# encoder.net
KiCad netlist of a schematic drawn in Altium Designer
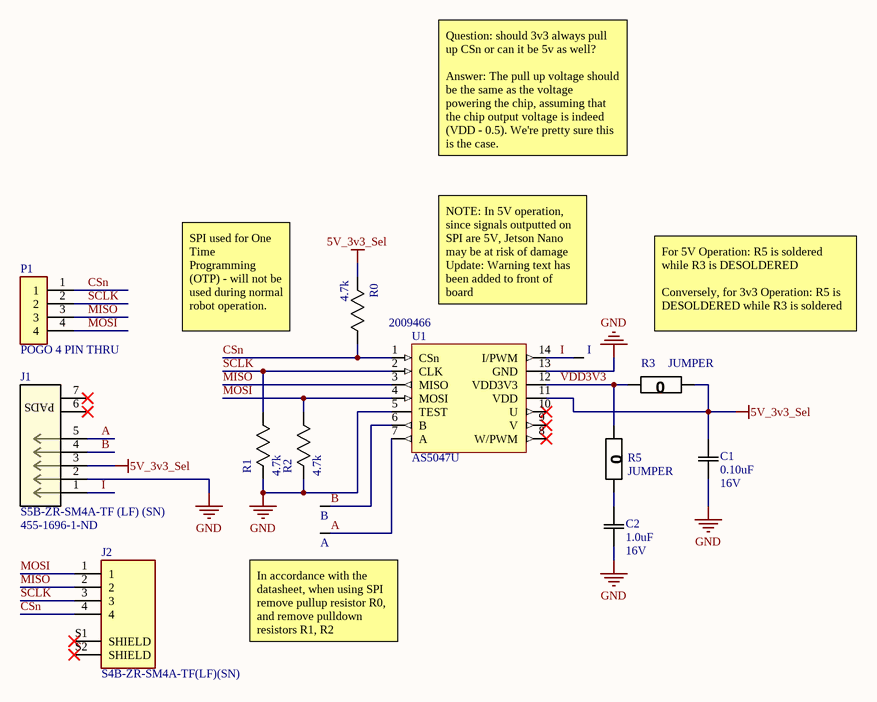
[diagram p0: encoder.SchDoc]

(export (version "E")
  (design (tool "Eeschema 10.0.6"))
  (components
    (comp (ref "A")
      (value "Test Point (Via)")
      (footprint "TP")
      (libsource (lib "AltiumLibraries") (part "Test Point (Via)"))
    )
    (comp (ref "B")
      (value "Test Point (Via)")
      (footprint "TP")
      (libsource (lib "AltiumLibraries") (part "Test Point (Via)"))
    )
    (comp (ref "C1")
      (value "0.10uF")
      (footprint "0603")
      (description "CAP CER 0.10UF 16V X5R 0603/0805")
      (fields (field (name "TOLERANCE") "10%") (field (name "RATING") "16V"))
      (libsource (lib "AltiumLibraries") (part "CAP 0.10uF 16V"))
    )
    (comp (ref "C2")
      (value "1.0uF")
      (footprint "0603")
      (description "CAP CER 1.0UF 16V X5R 0603/0805")
      (fields (field (name "TOLERANCE") "10%") (field (name "RATING") "16V"))
      (libsource (lib "AltiumLibraries") (part "CAP 1.0uF 16V"))
    )
    (comp (ref "I")
      (value "Test Point (Via)")
      (footprint "TP")
      (libsource (lib "AltiumLibraries") (part "Test Point (Via)"))
    )
    (comp (ref "J1")
      (value "S5B-ZR-SM4A-TF (LF) (SN)")
      (footprint "JST_S5B-ZR-SM4A-TF")
      (description "Connector Header Surface Mount, Right Angle 5 position 0.059\" (1.50mm)")
      (fields
        (field (name "SUPPLIER PART NUMBER 1") "455-1696-1-ND")
        (field (name "COPYRIGHT") "Copyright (C) 2021 Ultra Librarian. All rights reserved.")
      )
      (libsource (lib "AltiumLibraries") (part "CN 5POS JST ZR RA"))
    )
    (comp (ref "J2")
      (value "S4B-ZR-SM4A-TF(LF)(SN)")
      (footprint "JST_S4B-ZR-SM4A-TF(LF)(SN)")
      (description "Connector Header Surface Mount, Right Angle 4 position 0.059 (1.50mm)")
      (fields (field (name "MF") "JST Sales"))
      (libsource (lib "AltiumLibraries") (part "S4B-ZR-SM4A-TF(LF)(SN)"))
    )
    (comp (ref "P1")
      (value "POGO 4 PIN THRU")
      (footprint "POGO 4 PIN THRU")
      (description "4 pin POGO Holes 0.100\" Pitch")
      (libsource (lib "AltiumLibraries") (part "POGO 4 PIN THRU"))
    )
    (comp (ref "R0")
      (value "4.7k")
      (footprint "0603")
      (description "RES SMD 4.7k OHM 5% 1/8W 0805")
      (fields (field (name "TOLERANCE") "5%"))
      (libsource (lib "AltiumLibraries") (part "RES 4.7k 1/8W - 5%"))
    )
    (comp (ref "R1")
      (value "4.7k")
      (footprint "0603")
      (description "RES SMD 4.7k OHM 5% 1/8W 0805")
      (fields (field (name "TOLERANCE") "5%"))
      (libsource (lib "AltiumLibraries") (part "RES 4.7k 1/8W - 5%"))
    )
    (comp (ref "R2")
      (value "4.7k")
      (footprint "0603")
      (description "RES SMD 4.7k OHM 5% 1/8W 0805")
      (fields (field (name "TOLERANCE") "5%"))
      (libsource (lib "") (part "RES 4.7k 1/8W - 5%_1"))
    )
    (comp (ref "R3")
      (value "JUMPER")
      (footprint "0603")
      (description "RES SMD 0 OHM JUMPER GENERIC 0805/0603")
      (libsource (lib "AltiumLibraries") (part "RES 0 JUMPER"))
    )
    (comp (ref "R5")
      (value "JUMPER")
      (footprint "0603")
      (description "RES SMD 0 OHM JUMPER GENERIC 0805/0603")
      (libsource (lib "AltiumLibraries") (part "RES 0 JUMPER"))
    )
    (comp (ref "U1")
      (value "AS5047U")
      (footprint "AS5047U")
      (description "14-Bit On-Axis Magnetic Rotary Position Sensor with Up to 14-Bit Binary Incremental Pulse Count")
      (fields (field (name "SUPPLIER PART NUMBER 1") "2009466"))
      (libsource (lib "AltiumLibraries") (part "AS5047U"))
    )
  )
  (nets
    (net (code "1") (name "/A") (class "Default")
      (node (ref "A") (pin "1") (pinfunction "1_1") (pintype "passive"))
      (node (ref "J1") (pin "5") (pinfunction "5_5") (pintype "passive"))
      (node (ref "U1") (pin "7") (pinfunction "A_7") (pintype "output"))
    )
    (net (code "2") (name "/B") (class "Default")
      (node (ref "B") (pin "1") (pinfunction "1_1") (pintype "passive"))
      (node (ref "J1") (pin "4") (pinfunction "4_4") (pintype "passive"))
      (node (ref "U1") (pin "6") (pinfunction "B_6") (pintype "output"))
    )
    (net (code "3") (name "/CSn") (class "Default")
      (node (ref "J2") (pin "4") (pinfunction "4_4") (pintype "passive"))
      (node (ref "P1") (pin "1") (pinfunction "1_1") (pintype "passive"))
      (node (ref "R0") (pin "1") (pinfunction "R1_1") (pintype "passive"))
      (node (ref "U1") (pin "1") (pinfunction "CSn_1") (pintype "input"))
    )
    (net (code "4") (name "/I") (class "Default")
      (node (ref "I") (pin "1") (pinfunction "1_1") (pintype "passive"))
      (node (ref "J1") (pin "1") (pinfunction "1_1") (pintype "passive"))
      (node (ref "U1") (pin "14") (pinfunction "I/PWM_14") (pintype "output"))
    )
    (net (code "5") (name "/MISO") (class "Default")
      (node (ref "J2") (pin "2") (pinfunction "2_2") (pintype "passive"))
      (node (ref "P1") (pin "3") (pinfunction "3_3") (pintype "passive"))
      (node (ref "U1") (pin "3") (pinfunction "MISO_3") (pintype "output"))
    )
    (net (code "6") (name "/MOSI") (class "Default")
      (node (ref "J2") (pin "1") (pinfunction "1_1") (pintype "passive"))
      (node (ref "P1") (pin "4") (pinfunction "4_4") (pintype "passive"))
      (node (ref "R2") (pin "1") (pinfunction "R1_1") (pintype "passive"))
      (node (ref "U1") (pin "4") (pinfunction "MOSI_4") (pintype "input"))
    )
    (net (code "7") (name "/SCLK") (class "Default")
      (node (ref "J2") (pin "3") (pinfunction "3_3") (pintype "passive"))
      (node (ref "P1") (pin "2") (pinfunction "2_2") (pintype "passive"))
      (node (ref "R1") (pin "1") (pinfunction "R1_1") (pintype "passive"))
      (node (ref "U1") (pin "2") (pinfunction "CLK_2") (pintype "input"))
    )
    (net (code "8") (name "/VDD3V3") (class "Default")
      (node (ref "R3") (pin "2") (pinfunction "R2_2") (pintype "passive"))
      (node (ref "R5") (pin "1") (pinfunction "R1_1") (pintype "passive"))
      (node (ref "U1") (pin "12") (pinfunction "VDD3V3_12") (pintype "passive"))
    )
    (net (code "9") (name "5V_3v3_Sel") (class "Default")
      (node (ref "C1") (pin "2") (pinfunction "C2_2") (pintype "passive"))
      (node (ref "J1") (pin "3") (pinfunction "3_3") (pintype "passive"))
      (node (ref "R0") (pin "2") (pinfunction "R2_2") (pintype "passive"))
      (node (ref "R3") (pin "1") (pinfunction "R1_1") (pintype "passive"))
      (node (ref "U1") (pin "11") (pinfunction "VDD_11") (pintype "passive"))
    )
    (net (code "10") (name "GND") (class "Default")
      (node (ref "C1") (pin "1") (pinfunction "C1_1") (pintype "passive"))
      (node (ref "C2") (pin "2") (pinfunction "C2_2") (pintype "passive"))
      (node (ref "J1") (pin "2") (pinfunction "2_2") (pintype "passive"))
      (node (ref "R1") (pin "2") (pinfunction "R2_2") (pintype "passive"))
      (node (ref "R2") (pin "2") (pinfunction "R2_2") (pintype "passive"))
      (node (ref "U1") (pin "13") (pinfunction "GND_13") (pintype "passive"))
      (node (ref "U1") (pin "5") (pinfunction "TEST_5") (pintype "passive"))
    )
    (net (code "11") (name "Net-(C2-C1)") (class "Default")
      (node (ref "C2") (pin "1") (pinfunction "C1_1") (pintype "passive"))
      (node (ref "R5") (pin "2") (pinfunction "R2_2") (pintype "passive"))
    )
    (net (code "12") (name "unconnected-(J1-Pad6)") (class "Default")
      (node (ref "J1") (pin "6") (pinfunction "6_6") (pintype "passive+no_connect"))
    )
    (net (code "13") (name "unconnected-(J1-Pad7)") (class "Default")
      (node (ref "J1") (pin "7") (pinfunction "7_7") (pintype "passive+no_connect"))
    )
    (net (code "14") (name "unconnected-(J2-SHIELD-PadS1)") (class "Default")
      (node (ref "J2") (pin "S1") (pinfunction "SHIELD_S1") (pintype "passive+no_connect"))
    )
    (net (code "15") (name "unconnected-(J2-SHIELD-PadS2)") (class "Default")
      (node (ref "J2") (pin "S2") (pinfunction "SHIELD_S2") (pintype "passive+no_connect"))
    )
    (net (code "16") (name "unconnected-(U1-U-Pad10)") (class "Default")
      (node (ref "U1") (pin "10") (pinfunction "U_10") (pintype "output+no_connect"))
    )
    (net (code "17") (name "unconnected-(U1-V-Pad9)") (class "Default")
      (node (ref "U1") (pin "9") (pinfunction "V_9") (pintype "output+no_connect"))
    )
    (net (code "18") (name "unconnected-(U1-W{slash}PWM-Pad8)") (class "Default")
      (node (ref "U1") (pin "8") (pinfunction "W/PWM_8") (pintype "output+no_connect"))
    )
  )
)
